# StationModule.net
KiCad netlist of a schematic drawn in EAGLE
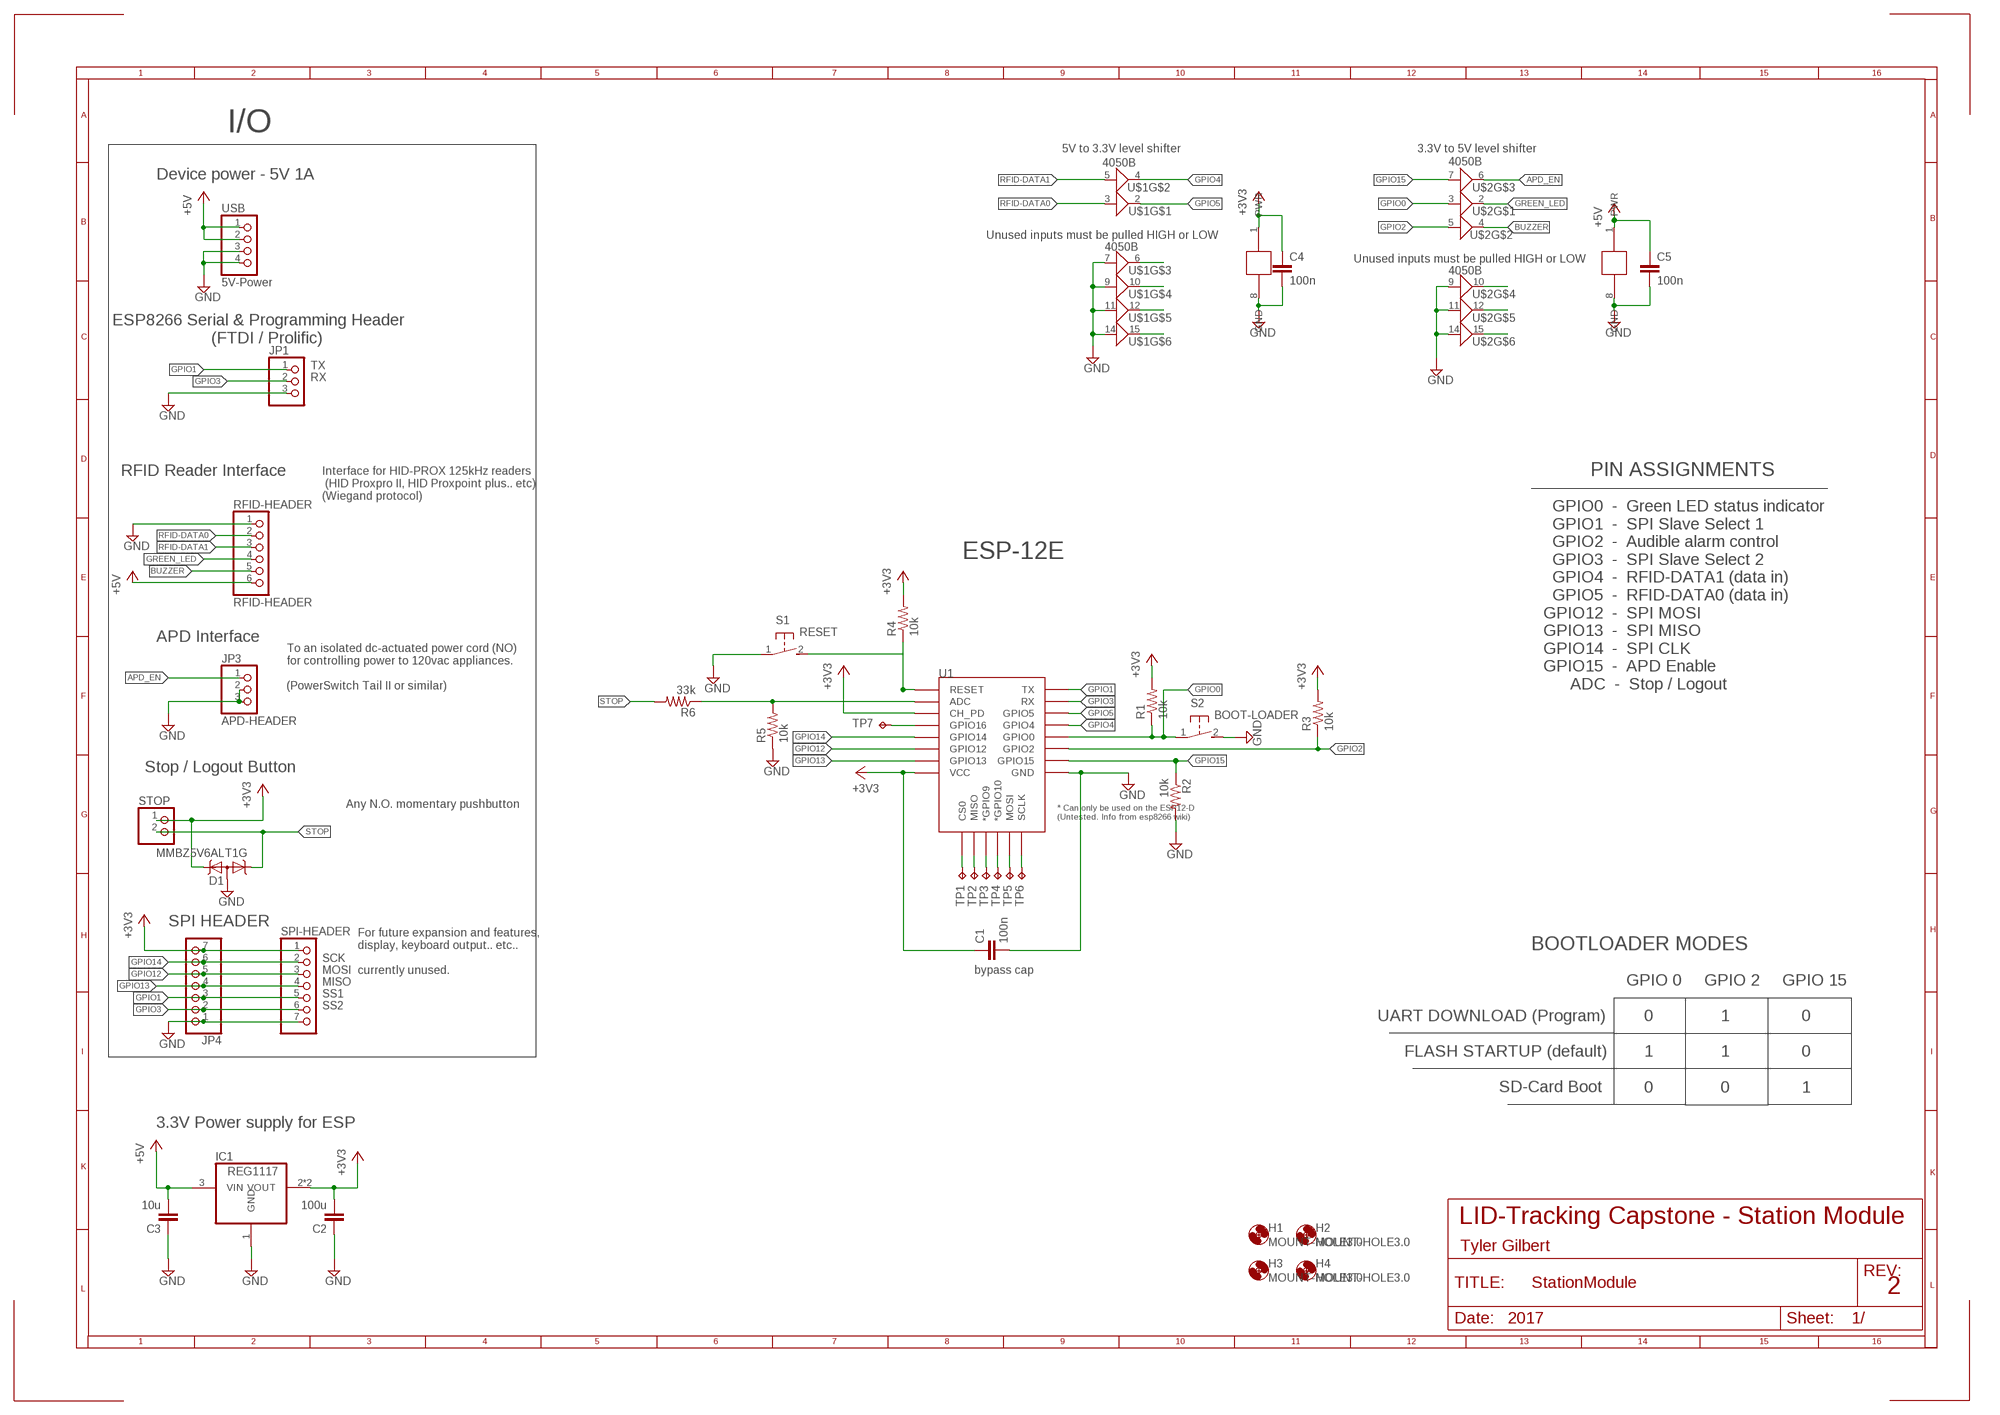
[diagram p0: schematic, sheet 1]

(export (version "E")
  (design (tool "Eeschema 10.0.6"))
  (components
    (comp (ref "C1")
      (value "100n")
      (footprint "eagle-import:C0805K")
      (libsource (lib "eagle-import") (part "C-EUC0805K"))
    )
    (comp (ref "C2")
      (value "100u")
      (footprint "eagle-import:C0805K")
      (libsource (lib "eagle-import") (part "C-EUC0805K"))
    )
    (comp (ref "C3")
      (value "10u")
      (footprint "eagle-import:C0805K")
      (libsource (lib "eagle-import") (part "C-EUC0805K"))
    )
    (comp (ref "C4")
      (value "100n")
      (footprint "eagle-import:C0805K")
      (libsource (lib "eagle-import") (part "C-EUC0805K"))
    )
    (comp (ref "C5")
      (value "100n")
      (footprint "eagle-import:C0805K")
      (libsource (lib "eagle-import") (part "C-EUC0805K"))
    )
    (comp (ref "D1")
      (value "MMBZ5V6ALT1G")
      (footprint "eagle-import:SOT23")
      (libsource (lib "eagle-import") (part "BAS40-06"))
    )
    (comp (ref "H1")
      (value "MOUNT-HOLE3.0")
      (footprint "eagle-import:3,0")
      (libsource (lib "eagle-import") (part "MOUNT-HOLE3.0"))
    )
    (comp (ref "H2")
      (value "MOUNT-HOLE3.0")
      (footprint "eagle-import:3,0")
      (libsource (lib "eagle-import") (part "MOUNT-HOLE3.0"))
    )
    (comp (ref "H3")
      (value "MOUNT-HOLE3.0")
      (footprint "eagle-import:3,0")
      (libsource (lib "eagle-import") (part "MOUNT-HOLE3.0"))
    )
    (comp (ref "H4")
      (value "MOUNT-HOLE3.0")
      (footprint "eagle-import:3,0")
      (libsource (lib "eagle-import") (part "MOUNT-HOLE3.0"))
    )
    (comp (ref "IC1")
      (value "REG1117")
      (footprint "eagle-import:SOT223")
      (libsource (lib "eagle-import") (part "REG1117"))
    )
    (comp (ref "JP1")
      (value "PINHD-1X3")
      (footprint "eagle-import:1X03")
      (libsource (lib "eagle-import") (part "pinhead+_PINHD-1X3"))
    )
    (comp (ref "JP3")
      (value "APD-HEADER")
      (footprint "eagle-import:1X03")
      (libsource (lib "eagle-import") (part "PINHD-1X3"))
    )
    (comp (ref "JP4")
      (value "PINHD-1X7")
      (footprint "eagle-import:1X07")
      (libsource (lib "eagle-import") (part "PINHD-1X7"))
    )
    (comp (ref "R1")
      (value "10k")
      (footprint "eagle-import:R0805")
      (libsource (lib "eagle-import") (part "R-US_R0805"))
    )
    (comp (ref "R2")
      (value "10k")
      (footprint "eagle-import:R0805")
      (libsource (lib "eagle-import") (part "R-US_R0805"))
    )
    (comp (ref "R3")
      (value "10k")
      (footprint "eagle-import:R0805")
      (libsource (lib "eagle-import") (part "R-US_R0805"))
    )
    (comp (ref "R4")
      (value "10k")
      (footprint "eagle-import:R0805")
      (libsource (lib "eagle-import") (part "R-US_R0805"))
    )
    (comp (ref "R5")
      (value "10k")
      (footprint "eagle-import:R0805")
      (libsource (lib "eagle-import") (part "R-US_R0805"))
    )
    (comp (ref "R6")
      (value "33k")
      (footprint "eagle-import:R0805")
      (libsource (lib "eagle-import") (part "R-US_R0805"))
    )
    (comp (ref "RFID-HEADER")
      (value "RFID-HEADER")
      (footprint "eagle-import:1X06")
      (libsource (lib "eagle-import") (part "PINHD-1X6"))
    )
    (comp (ref "S1")
      (value "RESET")
      (footprint "eagle-import:DTSM-3")
      (libsource (lib "eagle-import") (part "DTSM-3"))
    )
    (comp (ref "S2")
      (value "BOOT-LOADER")
      (footprint "eagle-import:DTSM-3")
      (libsource (lib "eagle-import") (part "DTSM-3"))
    )
    (comp (ref "SPI-HEADER")
      (value "PINHD-1X7")
      (footprint "eagle-import:1X07")
      (libsource (lib "eagle-import") (part "PINHD-1X7"))
    )
    (comp (ref "STOP")
      (value "PINHD-1X2")
      (footprint "eagle-import:1X02")
      (libsource (lib "eagle-import") (part "PINHD-1X2"))
    )
    (comp (ref "TP1")
      (value "TPB1,27")
      (footprint "eagle-import:B1,27")
      (libsource (lib "eagle-import") (part "TPB1,27"))
    )
    (comp (ref "TP2")
      (value "TPB1,27")
      (footprint "eagle-import:B1,27")
      (libsource (lib "eagle-import") (part "TPB1,27"))
    )
    (comp (ref "TP3")
      (value "TPB1,27")
      (footprint "eagle-import:B1,27")
      (libsource (lib "eagle-import") (part "TPB1,27"))
    )
    (comp (ref "TP4")
      (value "TPB1,27")
      (footprint "eagle-import:B1,27")
      (libsource (lib "eagle-import") (part "TPB1,27"))
    )
    (comp (ref "TP5")
      (value "TPB1,27")
      (footprint "eagle-import:B1,27")
      (libsource (lib "eagle-import") (part "TPB1,27"))
    )
    (comp (ref "TP6")
      (value "TPB1,27")
      (footprint "eagle-import:B1,27")
      (libsource (lib "eagle-import") (part "TPB1,27"))
    )
    (comp (ref "TP7")
      (value "TPB1,27")
      (footprint "eagle-import:B1,27")
      (libsource (lib "eagle-import") (part "TPB1,27"))
    )
    (comp (ref "U$1")
      (value "4050B")
      (footprint "eagle-import:SOIC16N")
      (libsource (lib "eagle-import") (part "4050B"))
    )
    (comp (ref "U$2")
      (value "4050B")
      (footprint "eagle-import:SOIC16N")
      (libsource (lib "eagle-import") (part "4050B"))
    )
    (comp (ref "U1")
      (value "ESP12ESMD")
      (footprint "eagle-import:ESP12E-SMD")
      (libsource (lib "eagle-import") (part "ESP12ESMD"))
    )
    (comp (ref "USB")
      (value "5V-Power")
      (footprint "eagle-import:1X04")
      (libsource (lib "eagle-import") (part "PINHD-1X4"))
    )
  )
  (nets
    (net (code "1") (name "+3V3") (class "Default")
      (node (ref "C1") (pin "1") (pinfunction "1_1") (pintype "passive"))
      (node (ref "C2") (pin "2") (pinfunction "2_2") (pintype "passive"))
      (node (ref "C4") (pin "1") (pinfunction "1_1") (pintype "passive"))
      (node (ref "D1") (pin "2") (pinfunction "K2_2") (pintype "passive"))
      (node (ref "IC1") (pin "2") (pinfunction "VOUT_2") (pintype "output"))
      (node (ref "IC1") (pin "4") (pinfunction "VOUT_4") (pintype "output"))
      (node (ref "JP4") (pin "7") (pinfunction "7_7") (pintype "passive"))
      (node (ref "R1") (pin "2") (pinfunction "2_2") (pintype "passive"))
      (node (ref "R3") (pin "2") (pinfunction "2_2") (pintype "passive"))
      (node (ref "R4") (pin "2") (pinfunction "2_2") (pintype "passive"))
      (node (ref "SPI-HEADER") (pin "1") (pinfunction "1_1") (pintype "passive"))
      (node (ref "STOP") (pin "1") (pinfunction "1_1") (pintype "passive"))
      (node (ref "U$1") (pin "1") (pinfunction "PWR_1") (pintype "power_in"))
      (node (ref "U1") (pin "CH_PD") (pinfunction "CH_PD_CH_PD") (pintype "bidirectional"))
      (node (ref "U1") (pin "VCC") (pinfunction "VCC_VCC") (pintype "bidirectional"))
    )
    (net (code "2") (name "+5V") (class "Default")
      (node (ref "C3") (pin "2") (pinfunction "2_2") (pintype "passive"))
      (node (ref "C5") (pin "1") (pinfunction "1_1") (pintype "passive"))
      (node (ref "IC1") (pin "3") (pinfunction "VIN_3") (pintype "input"))
      (node (ref "RFID-HEADER") (pin "6") (pinfunction "6_6") (pintype "passive"))
      (node (ref "U$2") (pin "1") (pinfunction "PWR_1") (pintype "power_in"))
      (node (ref "USB") (pin "1") (pinfunction "1_1") (pintype "passive"))
      (node (ref "USB") (pin "2") (pinfunction "2_2") (pintype "passive"))
    )
    (net (code "3") (name "APD_EN") (class "Default")
      (node (ref "JP3") (pin "1") (pinfunction "1_1") (pintype "passive"))
      (node (ref "U$2") (pin "6") (pinfunction "P$2_6") (pintype "output"))
    )
    (net (code "4") (name "BUZZER") (class "Default")
      (node (ref "RFID-HEADER") (pin "5") (pinfunction "5_5") (pintype "passive"))
      (node (ref "U$2") (pin "4") (pinfunction "P$2_4") (pintype "output"))
    )
    (net (code "5") (name "GND") (class "Default")
      (node (ref "C1") (pin "2") (pinfunction "2_2") (pintype "passive"))
      (node (ref "C2") (pin "1") (pinfunction "1_1") (pintype "passive"))
      (node (ref "C3") (pin "1") (pinfunction "1_1") (pintype "passive"))
      (node (ref "C4") (pin "2") (pinfunction "2_2") (pintype "passive"))
      (node (ref "C5") (pin "2") (pinfunction "2_2") (pintype "passive"))
      (node (ref "D1") (pin "3") (pinfunction "AA_3") (pintype "passive"))
      (node (ref "IC1") (pin "1") (pinfunction "GND_1") (pintype "power_in"))
      (node (ref "JP1") (pin "3") (pinfunction "3_3") (pintype "passive"))
      (node (ref "JP3") (pin "2") (pinfunction "2_2") (pintype "passive"))
      (node (ref "JP3") (pin "3") (pinfunction "3_3") (pintype "passive"))
      (node (ref "JP4") (pin "1") (pinfunction "1_1") (pintype "passive"))
      (node (ref "R2") (pin "2") (pinfunction "2_2") (pintype "passive"))
      (node (ref "R5") (pin "1") (pinfunction "1_1") (pintype "passive"))
      (node (ref "RFID-HEADER") (pin "1") (pinfunction "1_1") (pintype "passive"))
      (node (ref "S1") (pin "1") (pinfunction "1_1") (pintype "passive"))
      (node (ref "S2") (pin "2") (pinfunction "2_2") (pintype "passive"))
      (node (ref "SPI-HEADER") (pin "7") (pinfunction "7_7") (pintype "passive"))
      (node (ref "U$1") (pin "11") (pinfunction "P$1_11") (pintype "input"))
      (node (ref "U$1") (pin "14") (pinfunction "P$1_14") (pintype "input"))
      (node (ref "U$1") (pin "7") (pinfunction "P$1_7") (pintype "input"))
      (node (ref "U$1") (pin "8") (pinfunction "GND_8") (pintype "power_in"))
      (node (ref "U$1") (pin "9") (pinfunction "P$1_9") (pintype "input"))
      (node (ref "U$2") (pin "11") (pinfunction "P$1_11") (pintype "input"))
      (node (ref "U$2") (pin "14") (pinfunction "P$1_14") (pintype "input"))
      (node (ref "U$2") (pin "8") (pinfunction "GND_8") (pintype "power_in"))
      (node (ref "U$2") (pin "9") (pinfunction "P$1_9") (pintype "input"))
      (node (ref "U1") (pin "GND") (pinfunction "GND_GND") (pintype "bidirectional"))
      (node (ref "USB") (pin "3") (pinfunction "3_3") (pintype "passive"))
      (node (ref "USB") (pin "4") (pinfunction "4_4") (pintype "passive"))
    )
    (net (code "6") (name "GPIO0") (class "Default")
      (node (ref "R1") (pin "1") (pinfunction "1_1") (pintype "passive"))
      (node (ref "S2") (pin "1") (pinfunction "1_1") (pintype "passive"))
      (node (ref "U$2") (pin "3") (pinfunction "P$1_3") (pintype "input"))
      (node (ref "U1") (pin "GPIO0") (pinfunction "GPIO0_GPIO0") (pintype "bidirectional"))
    )
    (net (code "7") (name "GPIO1") (class "Default")
      (node (ref "JP1") (pin "1") (pinfunction "1_1") (pintype "passive"))
      (node (ref "JP4") (pin "3") (pinfunction "3_3") (pintype "passive"))
      (node (ref "SPI-HEADER") (pin "5") (pinfunction "5_5") (pintype "passive"))
      (node (ref "U1") (pin "TXD0") (pinfunction "TX_TXD0") (pintype "bidirectional"))
    )
    (net (code "8") (name "GPIO2") (class "Default")
      (node (ref "R3") (pin "1") (pinfunction "1_1") (pintype "passive"))
      (node (ref "U$2") (pin "5") (pinfunction "P$1_5") (pintype "input"))
      (node (ref "U1") (pin "GPIO2") (pinfunction "GPIO2_GPIO2") (pintype "bidirectional"))
    )
    (net (code "9") (name "GPIO3") (class "Default")
      (node (ref "JP1") (pin "2") (pinfunction "2_2") (pintype "passive"))
      (node (ref "JP4") (pin "2") (pinfunction "2_2") (pintype "passive"))
      (node (ref "SPI-HEADER") (pin "6") (pinfunction "6_6") (pintype "passive"))
      (node (ref "U1") (pin "RXD0") (pinfunction "RX_RXD0") (pintype "bidirectional"))
    )
    (net (code "10") (name "GPIO4") (class "Default")
      (node (ref "U$1") (pin "4") (pinfunction "P$2_4") (pintype "output"))
      (node (ref "U1") (pin "GPIO4") (pinfunction "GPIO4_GPIO4") (pintype "bidirectional"))
    )
    (net (code "11") (name "GPIO5") (class "Default")
      (node (ref "U$1") (pin "2") (pinfunction "P$2_2") (pintype "output"))
      (node (ref "U1") (pin "GPIO5") (pinfunction "GPIO5_GPIO5") (pintype "bidirectional"))
    )
    (net (code "12") (name "GPIO12") (class "Default")
      (node (ref "JP4") (pin "5") (pinfunction "5_5") (pintype "passive"))
      (node (ref "SPI-HEADER") (pin "3") (pinfunction "3_3") (pintype "passive"))
      (node (ref "U1") (pin "GPIO12") (pinfunction "GPIO12_GPIO12") (pintype "bidirectional"))
    )
    (net (code "13") (name "GPIO13") (class "Default")
      (node (ref "JP4") (pin "4") (pinfunction "4_4") (pintype "passive"))
      (node (ref "SPI-HEADER") (pin "4") (pinfunction "4_4") (pintype "passive"))
      (node (ref "U1") (pin "GPIO13") (pinfunction "GPIO13_GPIO13") (pintype "bidirectional"))
    )
    (net (code "14") (name "GPIO14") (class "Default")
      (node (ref "JP4") (pin "6") (pinfunction "6_6") (pintype "passive"))
      (node (ref "SPI-HEADER") (pin "2") (pinfunction "2_2") (pintype "passive"))
      (node (ref "U1") (pin "GPIO14") (pinfunction "GPIO14_GPIO14") (pintype "bidirectional"))
    )
    (net (code "15") (name "GPIO15") (class "Default")
      (node (ref "R2") (pin "1") (pinfunction "1_1") (pintype "passive"))
      (node (ref "U$2") (pin "7") (pinfunction "P$1_7") (pintype "input"))
      (node (ref "U1") (pin "GPIO15") (pinfunction "GPIO15_GPIO15") (pintype "bidirectional"))
    )
    (net (code "16") (name "GREEN_LED") (class "Default")
      (node (ref "RFID-HEADER") (pin "4") (pinfunction "4_4") (pintype "passive"))
      (node (ref "U$2") (pin "2") (pinfunction "P$2_2") (pintype "output"))
    )
    (net (code "17") (name "Net-(R4-Pad1)") (class "Default")
      (node (ref "R4") (pin "1") (pinfunction "1_1") (pintype "passive"))
      (node (ref "S1") (pin "2") (pinfunction "2_2") (pintype "passive"))
      (node (ref "U1") (pin "RESET") (pinfunction "RESET_RESET") (pintype "bidirectional"))
    )
    (net (code "18") (name "Net-(R5-Pad2)") (class "Default")
      (node (ref "R5") (pin "2") (pinfunction "2_2") (pintype "passive"))
      (node (ref "R6") (pin "1") (pinfunction "1_1") (pintype "passive"))
      (node (ref "U1") (pin "ADC") (pinfunction "ADC_ADC") (pintype "bidirectional"))
    )
    (net (code "19") (name "Net-(TP1-PadTP)") (class "Default")
      (node (ref "TP1") (pin "TP") (pinfunction "TP_TP") (pintype "input"))
      (node (ref "U1") (pin "CS0") (pinfunction "CS0_CS0") (pintype "bidirectional"))
    )
    (net (code "20") (name "Net-(TP2-PadTP)") (class "Default")
      (node (ref "TP2") (pin "TP") (pinfunction "TP_TP") (pintype "input"))
      (node (ref "U1") (pin "MISO") (pinfunction "MISO_MISO") (pintype "bidirectional"))
    )
    (net (code "21") (name "Net-(TP5-PadTP)") (class "Default")
      (node (ref "TP5") (pin "TP") (pinfunction "TP_TP") (pintype "input"))
      (node (ref "U1") (pin "MOSI") (pinfunction "MOSI_MOSI") (pintype "bidirectional"))
    )
    (net (code "22") (name "Net-(TP6-PadTP)") (class "Default")
      (node (ref "TP6") (pin "TP") (pinfunction "TP_TP") (pintype "input"))
      (node (ref "U1") (pin "SCLK") (pinfunction "SCLK_SCLK") (pintype "bidirectional"))
    )
    (net (code "23") (name "Net-(TP7-PadTP)") (class "Default")
      (node (ref "TP7") (pin "TP") (pinfunction "TP_TP") (pintype "input"))
      (node (ref "U1") (pin "GPIO16") (pinfunction "GPIO16_GPIO16") (pintype "bidirectional"))
    )
    (net (code "24") (name "Net-(U1-*GPIO9)") (class "Default")
      (node (ref "TP3") (pin "TP") (pinfunction "TP_TP") (pintype "input"))
      (node (ref "U1") (pin "GPIO9") (pinfunction "*GPIO9_GPIO9") (pintype "bidirectional"))
    )
    (net (code "25") (name "Net-(U1-*GPIO10)") (class "Default")
      (node (ref "TP4") (pin "TP") (pinfunction "TP_TP") (pintype "input"))
      (node (ref "U1") (pin "GPIO10") (pinfunction "*GPIO10_GPIO10") (pintype "bidirectional"))
    )
    (net (code "26") (name "RFID-DATA0") (class "Default")
      (node (ref "RFID-HEADER") (pin "2") (pinfunction "2_2") (pintype "passive"))
      (node (ref "U$1") (pin "3") (pinfunction "P$1_3") (pintype "input"))
    )
    (net (code "27") (name "RFID-DATA1") (class "Default")
      (node (ref "RFID-HEADER") (pin "3") (pinfunction "3_3") (pintype "passive"))
      (node (ref "U$1") (pin "5") (pinfunction "P$1_5") (pintype "input"))
    )
    (net (code "28") (name "STOP") (class "Default")
      (node (ref "D1") (pin "1") (pinfunction "K1_1") (pintype "passive"))
      (node (ref "R6") (pin "2") (pinfunction "2_2") (pintype "passive"))
      (node (ref "STOP") (pin "2") (pinfunction "2_2") (pintype "passive"))
    )
    (net (code "29") (name "unconnected-(U$1C-P$2-Pad6)") (class "Default")
      (node (ref "U$1") (pin "6") (pinfunction "P$2_6") (pintype "output"))
    )
    (net (code "30") (name "unconnected-(U$1D-P$2-Pad10)") (class "Default")
      (node (ref "U$1") (pin "10") (pinfunction "P$2_10") (pintype "output"))
    )
    (net (code "31") (name "unconnected-(U$1E-P$2-Pad12)") (class "Default")
      (node (ref "U$1") (pin "12") (pinfunction "P$2_12") (pintype "output"))
    )
    (net (code "32") (name "unconnected-(U$1F-P$2-Pad15)") (class "Default")
      (node (ref "U$1") (pin "15") (pinfunction "P$2_15") (pintype "output"))
    )
    (net (code "33") (name "unconnected-(U$2D-P$2-Pad10)") (class "Default")
      (node (ref "U$2") (pin "10") (pinfunction "P$2_10") (pintype "output"))
    )
    (net (code "34") (name "unconnected-(U$2E-P$2-Pad12)") (class "Default")
      (node (ref "U$2") (pin "12") (pinfunction "P$2_12") (pintype "output"))
    )
    (net (code "35") (name "unconnected-(U$2F-P$2-Pad15)") (class "Default")
      (node (ref "U$2") (pin "15") (pinfunction "P$2_15") (pintype "output"))
    )
  )
)
